# power_mux.net
KiCad netlist of a schematic drawn in Altium Designer
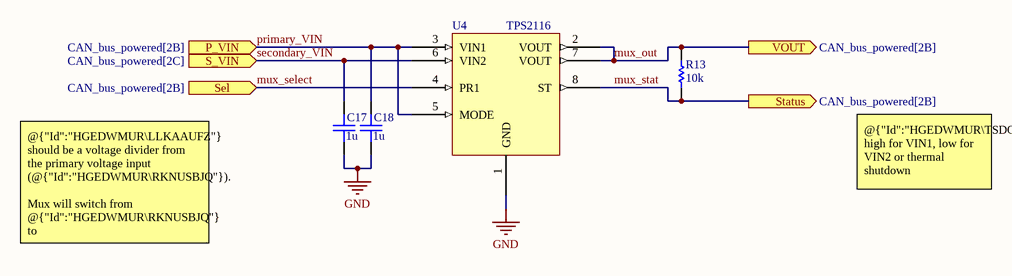
[diagram p0: power_mux.SchDoc]

(export (version "E")
  (design (tool "Eeschema 10.0.6"))
  (components
    (comp (ref "C17")
      (value "1u")
      (footprint "CAP-0603-NP")
      (description "Capacitor")
      (libsource (lib "drfc_schlib") (part "Capacitor"))
    )
    (comp (ref "C18")
      (value "1u")
      (footprint "CAP-0603-NP")
      (description "Capacitor")
      (libsource (lib "drfc_schlib") (part "Capacitor"))
    )
    (comp (ref "R13")
      (value "10k")
      (footprint "RES-0603")
      (description "Resistor")
      (libsource (lib "drfc_schlib") (part "Resistor"))
    )
    (comp (ref "U4")
      (value "TPS2116")
      (footprint "SOT-5x3")
      (description "1.6 V to 5.5 V, 2.5-A Low IQ Power Mux with Manual and Priority Switchover")
      (libsource (lib "drfc_schlib") (part "TPS2116"))
    )
  )
  (nets
    (net (code "1") (name "/mux_out") (class "Default")
      (node (ref "R13") (pin "2") (pinfunction "2_2") (pintype "passive"))
      (node (ref "U4") (pin "2") (pinfunction "VOUT_2") (pintype "output"))
      (node (ref "U4") (pin "7") (pinfunction "VOUT_7") (pintype "output"))
    )
    (net (code "2") (name "/mux_select") (class "Default")
      (node (ref "U4") (pin "4") (pinfunction "PR1_4") (pintype "input"))
    )
    (net (code "3") (name "/mux_stat") (class "Default")
      (node (ref "R13") (pin "1") (pinfunction "1_1") (pintype "passive"))
      (node (ref "U4") (pin "8") (pinfunction "ST_8") (pintype "output"))
    )
    (net (code "4") (name "/primary_VIN") (class "Default")
      (node (ref "C18") (pin "2") (pinfunction "2_2") (pintype "passive"))
      (node (ref "U4") (pin "3") (pinfunction "VIN1_3") (pintype "input"))
      (node (ref "U4") (pin "5") (pinfunction "MODE_5") (pintype "input"))
    )
    (net (code "5") (name "/secondary_VIN") (class "Default")
      (node (ref "C17") (pin "2") (pinfunction "2_2") (pintype "passive"))
      (node (ref "U4") (pin "6") (pinfunction "VIN2_6") (pintype "input"))
    )
    (net (code "6") (name "GND") (class "Default")
      (node (ref "C17") (pin "1") (pinfunction "1_1") (pintype "passive"))
      (node (ref "C18") (pin "1") (pinfunction "1_1") (pintype "passive"))
      (node (ref "U4") (pin "1") (pinfunction "GND_1") (pintype "power_in"))
    )
  )
)
